# Custom_USB_N64_smaller.net
KiCad netlist of a schematic drawn in EAGLE
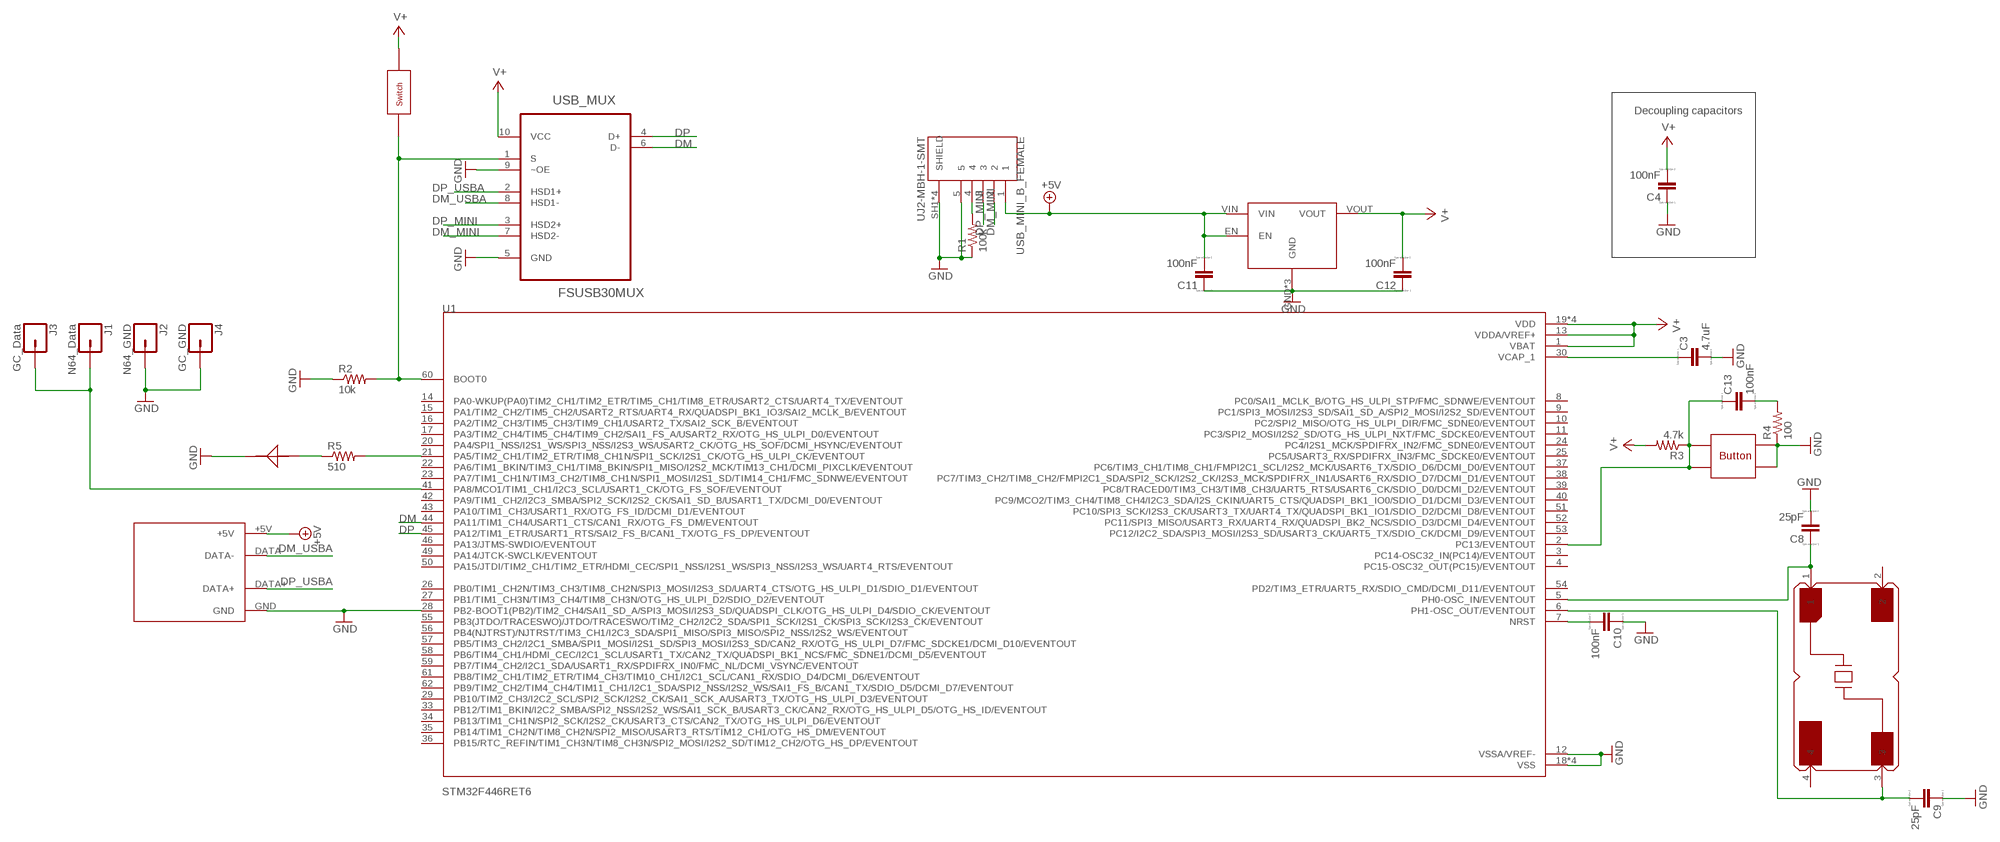
[diagram p0: schematic, sheet 1]

(export (version "E")
  (design (tool "Eeschema 10.0.6"))
  (components
    (comp (ref "C3")
      (value "4.7uF")
      (footprint "eagle-import:C0805")
      (libsource (lib "eagle-import") (part "C"))
    )
    (comp (ref "C4")
      (value "100nF")
      (footprint "eagle-import:C0805")
      (libsource (lib "eagle-import") (part "C"))
    )
    (comp (ref "C8")
      (value "25pF")
      (footprint "eagle-import:C0805")
      (libsource (lib "eagle-import") (part "C"))
    )
    (comp (ref "C9")
      (value "25pF")
      (footprint "eagle-import:C0805")
      (libsource (lib "eagle-import") (part "C"))
    )
    (comp (ref "C10")
      (value "100nF")
      (footprint "eagle-import:C0805")
      (libsource (lib "eagle-import") (part "C"))
    )
    (comp (ref "C11")
      (value "100nF")
      (footprint "eagle-import:C0805")
      (libsource (lib "eagle-import") (part "C"))
    )
    (comp (ref "C12")
      (value "100nF")
      (footprint "eagle-import:C0805")
      (libsource (lib "eagle-import") (part "C"))
    )
    (comp (ref "C13")
      (value "100nF")
      (footprint "eagle-import:C0805")
      (libsource (lib "eagle-import") (part "C"))
    )
    (comp (ref "CHANGE_CONTROLS")
      (value "PUSHBUTTON")
      (footprint "eagle-import:PUSHBUTTON")
      (libsource (lib "eagle-import") (part "PUSHBUTTON"))
    )
    (comp (ref "J1")
      (value "N64_Data")
      (footprint "eagle-import:1X01")
      (libsource (lib "eagle-import") (part "M01PTH"))
    )
    (comp (ref "J2")
      (value "N64_GND")
      (footprint "eagle-import:1X01")
      (libsource (lib "eagle-import") (part "M01PTH"))
    )
    (comp (ref "J3")
      (value "GC_Data")
      (footprint "eagle-import:1X01")
      (libsource (lib "eagle-import") (part "M01PTH"))
    )
    (comp (ref "J4")
      (value "GC_GND")
      (footprint "eagle-import:1X01")
      (libsource (lib "eagle-import") (part "M01PTH"))
    )
    (comp (ref "R1")
      (value "100k")
      (footprint "eagle-import:R0805")
      (libsource (lib "eagle-import") (part "R-US_R0805"))
    )
    (comp (ref "R2")
      (value "10k")
      (footprint "eagle-import:R0805")
      (libsource (lib "eagle-import") (part "R-US_R0805"))
    )
    (comp (ref "R3")
      (value "4.7k")
      (footprint "eagle-import:R0805")
      (libsource (lib "eagle-import") (part "R-US_R0805"))
    )
    (comp (ref "R4")
      (value "100")
      (footprint "eagle-import:R0805")
      (libsource (lib "eagle-import") (part "R-US_R0805"))
    )
    (comp (ref "R5")
      (value "510")
      (footprint "eagle-import:R0805")
      (libsource (lib "eagle-import") (part "R-US_R0805"))
    )
    (comp (ref "SWITCH")
      (value "DM01")
      (footprint "eagle-import:DM01")
      (libsource (lib "eagle-import") (part "DM01"))
    )
    (comp (ref "U$6")
      (value "17-21SYGC/S530-E2/TR8")
      (footprint "eagle-import:17-21SYGC_S530-E2_TR8")
      (libsource (lib "eagle-import") (part "17-21SYGC/S530-E2/TR8"))
    )
    (comp (ref "U1")
      (value "STM32F446RET6")
      (footprint "eagle-import:QFP50P1200X1200X160-64N")
      (fields (field (name "MF") "STMicroelectronics"))
      (libsource (lib "eagle-import") (part "STM32F446RET6"))
    )
    (comp (ref "USB_A_FEMALE")
      (value "USB_A_F")
      (footprint "eagle-import:USB_A_F")
      (libsource (lib "eagle-import") (part "USB_A_F"))
    )
    (comp (ref "USB_MINI_B_FEMALE")
      (value "UJ2-MBH-1-SMT")
      (footprint "eagle-import:CUI_UJ2-MBH-1-SMT")
      (fields (field (name "MF") "CUI") (field (name "MP") "UJ2-MBH-1-SMT-TR"))
      (libsource (lib "eagle-import") (part "UJ2-MBH-1-SMT"))
    )
    (comp (ref "USB_MUX")
      (value "FSUSB30MUX")
      (footprint "eagle-import:SOP50P490X110-10N")
      (fields (field (name "MF") "ON Semiconductor"))
      (libsource (lib "eagle-import") (part "FSUSB30MUX"))
    )
    (comp (ref "V_REG")
      (value "S-1172B33-U5T1G")
      (footprint "eagle-import:S-1172B33-U5T1G")
      (libsource (lib "eagle-import") (part "S-1172B33-U5T1G"))
    )
    (comp (ref "XTAL_HSE")
      (value "ABMM-8.000MHZ-B2-T")
      (footprint "eagle-import:DFN-4")
      (fields (field (name "MF") "Abracon"))
      (libsource (lib "eagle-import") (part "ABMM-8.000MHZ-B2-T"))
    )
  )
  (nets
    (net (code "1") (name "+5V") (class "Default")
      (node (ref "C11") (pin "2") (pinfunction "2_2") (pintype "passive"))
      (node (ref "USB_A_FEMALE") (pin "+5V") (pinfunction "+5V_+5V") (pintype "bidirectional"))
      (node (ref "USB_MINI_B_FEMALE") (pin "1") (pinfunction "1_1") (pintype "passive"))
      (node (ref "V_REG") (pin "EN") (pinfunction "EN_EN") (pintype "bidirectional"))
      (node (ref "V_REG") (pin "VIN") (pinfunction "VIN_VIN") (pintype "bidirectional"))
    )
    (net (code "2") (name "/DM") (class "Default")
      (node (ref "U1") (pin "44") (pinfunction "PA11/TIM1_CH4/USART1_CTS/CAN1_RX/OTG_FS_DM/EVENTOUT_44") (pintype "bidirectional"))
      (node (ref "USB_MUX") (pin "6") (pinfunction "D-_6") (pintype "bidirectional"))
    )
    (net (code "3") (name "/DM_MINI") (class "Default")
      (node (ref "USB_MINI_B_FEMALE") (pin "2") (pinfunction "2_2") (pintype "passive"))
      (node (ref "USB_MUX") (pin "7") (pinfunction "HSD2-_7") (pintype "bidirectional"))
    )
    (net (code "4") (name "/DM_USBA") (class "Default")
      (node (ref "USB_A_FEMALE") (pin "DATA-") (pinfunction "DATA-_DATA-") (pintype "bidirectional"))
      (node (ref "USB_MUX") (pin "8") (pinfunction "HSD1-_8") (pintype "bidirectional"))
    )
    (net (code "5") (name "/DP") (class "Default")
      (node (ref "U1") (pin "45") (pinfunction "PA12/TIM1_ETR/USART1_RTS/SAI2_FS_B/CAN1_TX/OTG_FS_DP/EVENTOUT_45") (pintype "bidirectional"))
      (node (ref "USB_MUX") (pin "4") (pinfunction "D+_4") (pintype "bidirectional"))
    )
    (net (code "6") (name "/DP_MINI") (class "Default")
      (node (ref "USB_MINI_B_FEMALE") (pin "3") (pinfunction "3_3") (pintype "passive"))
      (node (ref "USB_MUX") (pin "3") (pinfunction "HSD2+_3") (pintype "bidirectional"))
    )
    (net (code "7") (name "/DP_USBA") (class "Default")
      (node (ref "USB_A_FEMALE") (pin "DATA+") (pinfunction "DATA+_DATA+") (pintype "bidirectional"))
      (node (ref "USB_MUX") (pin "2") (pinfunction "HSD1+_2") (pintype "bidirectional"))
    )
    (net (code "8") (name "GND") (class "Default")
      (node (ref "C10") (pin "1") (pinfunction "1_1") (pintype "passive"))
      (node (ref "C11") (pin "1") (pinfunction "1_1") (pintype "passive"))
      (node (ref "C12") (pin "1") (pinfunction "1_1") (pintype "passive"))
      (node (ref "C3") (pin "2") (pinfunction "2_2") (pintype "passive"))
      (node (ref "C4") (pin "1") (pinfunction "1_1") (pintype "passive"))
      (node (ref "C8") (pin "2") (pinfunction "2_2") (pintype "passive"))
      (node (ref "C9") (pin "1") (pinfunction "1_1") (pintype "passive"))
      (node (ref "CHANGE_CONTROLS") (pin "P$3") (pinfunction "P$3_P$3") (pintype "bidirectional"))
      (node (ref "CHANGE_CONTROLS") (pin "P$4") (pinfunction "P$4_P$4") (pintype "bidirectional"))
      (node (ref "J2") (pin "1") (pinfunction "1_1") (pintype "passive"))
      (node (ref "J4") (pin "1") (pinfunction "1_1") (pintype "passive"))
      (node (ref "R1") (pin "1") (pinfunction "1_1") (pintype "passive"))
      (node (ref "R2") (pin "1") (pinfunction "1_1") (pintype "passive"))
      (node (ref "R4") (pin "1") (pinfunction "1_1") (pintype "passive"))
      (node (ref "U$6") (pin "NEG") (pinfunction "NEG_NEG") (pintype "bidirectional"))
      (node (ref "U1") (pin "12") (pinfunction "VSSA/VREF-_12") (pintype "power_in"))
      (node (ref "U1") (pin "18") (pinfunction "VSS_18") (pintype "power_in"))
      (node (ref "U1") (pin "28") (pinfunction "PB2-BOOT1(PB2)/TIM2_CH4/SAI1_SD_A/SPI3_MOSI/I2S3_SD/QUADSPI_CLK/OTG_HS_ULPI_D4/SDIO_CK/EVENTOUT_28") (pintype "bidirectional"))
      (node (ref "U1") (pin "31") (pinfunction "VSS_31") (pintype "power_in"))
      (node (ref "U1") (pin "47") (pinfunction "VSS_47") (pintype "power_in"))
      (node (ref "U1") (pin "63") (pinfunction "VSS_63") (pintype "power_in"))
      (node (ref "USB_A_FEMALE") (pin "GND") (pinfunction "GND_GND") (pintype "bidirectional"))
      (node (ref "USB_MINI_B_FEMALE") (pin "5") (pinfunction "5_5") (pintype "passive"))
      (node (ref "USB_MINI_B_FEMALE") (pin "SH1") (pinfunction "SHIELD_SH1") (pintype "passive"))
      (node (ref "USB_MINI_B_FEMALE") (pin "SH2") (pinfunction "SHIELD_SH2") (pintype "passive"))
      (node (ref "USB_MINI_B_FEMALE") (pin "SH3") (pinfunction "SHIELD_SH3") (pintype "passive"))
      (node (ref "USB_MINI_B_FEMALE") (pin "SH4") (pinfunction "SHIELD_SH4") (pintype "passive"))
      (node (ref "USB_MUX") (pin "5") (pinfunction "GND_5") (pintype "passive"))
      (node (ref "USB_MUX") (pin "9") (pinfunction "~{OE}_9") (pintype "input"))
      (node (ref "V_REG") (pin "GND") (pinfunction "GND_GND") (pintype "bidirectional"))
      (node (ref "V_REG") (pin "GND2") (pinfunction "GND_GND2") (pintype "bidirectional"))
      (node (ref "V_REG") (pin "GND3") (pinfunction "GND_GND3") (pintype "bidirectional"))
    )
    (net (code "9") (name "Net-(C13-Pad2)") (class "Default")
      (node (ref "C13") (pin "2") (pinfunction "2_2") (pintype "passive"))
      (node (ref "R4") (pin "2") (pinfunction "2_2") (pintype "passive"))
    )
    (net (code "10") (name "Net-(R1-Pad2)") (class "Default")
      (node (ref "R1") (pin "2") (pinfunction "2_2") (pintype "passive"))
      (node (ref "USB_MINI_B_FEMALE") (pin "4") (pinfunction "4_4") (pintype "passive"))
    )
    (net (code "11") (name "Net-(R5-Pad1)") (class "Default")
      (node (ref "R5") (pin "1") (pinfunction "1_1") (pintype "passive"))
      (node (ref "U$6") (pin "POS") (pinfunction "POS_POS") (pintype "bidirectional"))
    )
    (net (code "12") (name "Net-(U1-BOOT0)") (class "Default")
      (node (ref "R2") (pin "2") (pinfunction "2_2") (pintype "passive"))
      (node (ref "SWITCH") (pin "P$2") (pinfunction "P$2_P$2") (pintype "bidirectional"))
      (node (ref "U1") (pin "60") (pinfunction "BOOT0_60") (pintype "input"))
      (node (ref "USB_MUX") (pin "1") (pinfunction "S_1") (pintype "input"))
    )
    (net (code "13") (name "Net-(U1-NRST)") (class "Default")
      (node (ref "C10") (pin "2") (pinfunction "2_2") (pintype "passive"))
      (node (ref "U1") (pin "7") (pinfunction "NRST_7") (pintype "bidirectional"))
    )
    (net (code "14") (name "Net-(U1-PA5{slash}TIM2_CH1{slash}TIM2_ETR{slash}TIM8_CH1N{slash}SPI1_SCK{slash}I2S1_CK{slash}OTG_HS_ULPI_CK{slash}EVENTOUT)") (class "Default")
      (node (ref "R5") (pin "2") (pinfunction "2_2") (pintype "passive"))
      (node (ref "U1") (pin "21") (pinfunction "PA5/TIM2_CH1/TIM2_ETR/TIM8_CH1N/SPI1_SCK/I2S1_CK/OTG_HS_ULPI_CK/EVENTOUT_21") (pintype "bidirectional"))
    )
    (net (code "15") (name "Net-(U1-PA8{slash}MCO1{slash}TIM1_CH1{slash}I2C3_SCL{slash}USART1_CK{slash}OTG_FS_SOF{slash}EVENTOUT)") (class "Default")
      (node (ref "J1") (pin "1") (pinfunction "1_1") (pintype "passive"))
      (node (ref "J3") (pin "1") (pinfunction "1_1") (pintype "passive"))
      (node (ref "U1") (pin "41") (pinfunction "PA8/MCO1/TIM1_CH1/I2C3_SCL/USART1_CK/OTG_FS_SOF/EVENTOUT_41") (pintype "bidirectional"))
    )
    (net (code "16") (name "Net-(U1-PC13{slash}EVENTOUT)") (class "Default")
      (node (ref "C13") (pin "1") (pinfunction "1_1") (pintype "passive"))
      (node (ref "CHANGE_CONTROLS") (pin "P$1") (pinfunction "P$1_P$1") (pintype "bidirectional"))
      (node (ref "CHANGE_CONTROLS") (pin "P$2") (pinfunction "P$2_P$2") (pintype "bidirectional"))
      (node (ref "R3") (pin "1") (pinfunction "1_1") (pintype "passive"))
      (node (ref "U1") (pin "2") (pinfunction "PC13/EVENTOUT_2") (pintype "bidirectional"))
    )
    (net (code "17") (name "Net-(U1-PH0-OSC_IN{slash}EVENTOUT)") (class "Default")
      (node (ref "C8") (pin "1") (pinfunction "1_1") (pintype "passive"))
      (node (ref "U1") (pin "5") (pinfunction "PH0-OSC_IN/EVENTOUT_5") (pintype "bidirectional"))
      (node (ref "XTAL_HSE") (pin "1") (pinfunction "1_1") (pintype "bidirectional"))
    )
    (net (code "18") (name "Net-(U1-PH1-OSC_OUT{slash}EVENTOUT)") (class "Default")
      (node (ref "C9") (pin "2") (pinfunction "2_2") (pintype "passive"))
      (node (ref "U1") (pin "6") (pinfunction "PH1-OSC_OUT/EVENTOUT_6") (pintype "bidirectional"))
      (node (ref "XTAL_HSE") (pin "3") (pinfunction "3_3") (pintype "bidirectional"))
    )
    (net (code "19") (name "Net-(U1-VCAP_1)") (class "Default")
      (node (ref "C3") (pin "1") (pinfunction "1_1") (pintype "passive"))
      (node (ref "U1") (pin "30") (pinfunction "VCAP_1_30") (pintype "power_in"))
    )
    (net (code "20") (name "V+") (class "Default")
      (node (ref "C12") (pin "2") (pinfunction "2_2") (pintype "passive"))
      (node (ref "C4") (pin "2") (pinfunction "2_2") (pintype "passive"))
      (node (ref "R3") (pin "2") (pinfunction "2_2") (pintype "passive"))
      (node (ref "SWITCH") (pin "P$1") (pinfunction "P$1_P$1") (pintype "bidirectional"))
      (node (ref "U1") (pin "1") (pinfunction "VBAT_1") (pintype "power_in"))
      (node (ref "U1") (pin "13") (pinfunction "VDDA/VREF+_13") (pintype "power_in"))
      (node (ref "U1") (pin "19") (pinfunction "VDD_19") (pintype "power_in"))
      (node (ref "U1") (pin "32") (pinfunction "VDD_32") (pintype "power_in"))
      (node (ref "U1") (pin "48") (pinfunction "VDD_48") (pintype "power_in"))
      (node (ref "U1") (pin "64") (pinfunction "VDD_64") (pintype "power_in"))
      (node (ref "USB_MUX") (pin "10") (pinfunction "VCC_10") (pintype "power_in"))
      (node (ref "V_REG") (pin "VOUT") (pinfunction "VOUT_VOUT") (pintype "bidirectional"))
    )
    (net (code "21") (name "unconnected-(U1-PA0-WKUP(PA0)TIM2_CH1{slash}TIM2_ETR{slash}TIM5_CH1{slash}TIM8_ETR{slash}USART2_CTS{slash}UART4_TX{slash}EVENTOUT-Pad14)") (class "Default")
      (node (ref "U1") (pin "14") (pinfunction "PA0-WKUP(PA0)TIM2_CH1/TIM2_ETR/TIM5_CH1/TIM8_ETR/USART2_CTS/UART4_TX/EVENTOUT_14") (pintype "bidirectional"))
    )
    (net (code "22") (name "unconnected-(U1-PA1{slash}TIM2_CH2{slash}TIM5_CH2{slash}USART2_RTS{slash}UART4_RX{slash}QUADSPI_BK1_IO3{slash}SAI2_MCLK_B{slash}EVENTOUT-Pad15)") (class "Default")
      (node (ref "U1") (pin "15") (pinfunction "PA1/TIM2_CH2/TIM5_CH2/USART2_RTS/UART4_RX/QUADSPI_BK1_IO3/SAI2_MCLK_B/EVENTOUT_15") (pintype "bidirectional"))
    )
    (net (code "23") (name "unconnected-(U1-PA2{slash}TIM2_CH3{slash}TIM5_CH3{slash}TIM9_CH1{slash}USART2_TX{slash}SAI2_SCK_B{slash}EVENTOUT-Pad16)") (class "Default")
      (node (ref "U1") (pin "16") (pinfunction "PA2/TIM2_CH3/TIM5_CH3/TIM9_CH1/USART2_TX/SAI2_SCK_B/EVENTOUT_16") (pintype "bidirectional"))
    )
    (net (code "24") (name "unconnected-(U1-PA3{slash}TIM2_CH4{slash}TIM5_CH4{slash}TIM9_CH2{slash}SAI1_FS_A{slash}USART2_RX{slash}OTG_HS_ULPI_D0{slash}EVENTOUT-Pad17)") (class "Default")
      (node (ref "U1") (pin "17") (pinfunction "PA3/TIM2_CH4/TIM5_CH4/TIM9_CH2/SAI1_FS_A/USART2_RX/OTG_HS_ULPI_D0/EVENTOUT_17") (pintype "bidirectional"))
    )
    (net (code "25") (name "unconnected-(U1-PA4{slash}SPI1_NSS{slash}I2S1_WS{slash}SPI3_NSS{slash}I2S3_WS{slash}USART2_CK{slash}OTG_HS_SOF{slash}DCMI_HSYNC{slash}EVENTOUT-Pad20)") (class "Default")
      (node (ref "U1") (pin "20") (pinfunction "PA4/SPI1_NSS/I2S1_WS/SPI3_NSS/I2S3_WS/USART2_CK/OTG_HS_SOF/DCMI_HSYNC/EVENTOUT_20") (pintype "bidirectional"))
    )
    (net (code "26") (name "unconnected-(U1-PA6{slash}TIM1_BKIN{slash}TIM3_CH1{slash}TIM8_BKIN{slash}SPI1_MISO{slash}I2S2_MCK{slash}TIM13_CH1{slash}DCMI_PIXCLK{slash}EVENTOUT-Pad22)") (class "Default")
      (node (ref "U1") (pin "22") (pinfunction "PA6/TIM1_BKIN/TIM3_CH1/TIM8_BKIN/SPI1_MISO/I2S2_MCK/TIM13_CH1/DCMI_PIXCLK/EVENTOUT_22") (pintype "bidirectional"))
    )
    (net (code "27") (name "unconnected-(U1-PA7{slash}TIM1_CH1N{slash}TIM3_CH2{slash}TIM8_CH1N{slash}SPI1_MOSI{slash}I2S1_SD{slash}TIM14_CH1{slash}FMC_SDNWE{slash}EVENTOUT-Pad23)") (class "Default")
      (node (ref "U1") (pin "23") (pinfunction "PA7/TIM1_CH1N/TIM3_CH2/TIM8_CH1N/SPI1_MOSI/I2S1_SD/TIM14_CH1/FMC_SDNWE/EVENTOUT_23") (pintype "bidirectional"))
    )
    (net (code "28") (name "unconnected-(U1-PA9{slash}TIM1_CH2{slash}I2C3_SMBA{slash}SPI2_SCK{slash}I2S2_CK{slash}SAI1_SD_B{slash}USART1_TX{slash}DCMI_D0{slash}EVENTOUT-Pad42)") (class "Default")
      (node (ref "U1") (pin "42") (pinfunction "PA9/TIM1_CH2/I2C3_SMBA/SPI2_SCK/I2S2_CK/SAI1_SD_B/USART1_TX/DCMI_D0/EVENTOUT_42") (pintype "bidirectional"))
    )
    (net (code "29") (name "unconnected-(U1-PA10{slash}TIM1_CH3{slash}USART1_RX{slash}OTG_FS_ID{slash}DCMI_D1{slash}EVENTOUT-Pad43)") (class "Default")
      (node (ref "U1") (pin "43") (pinfunction "PA10/TIM1_CH3/USART1_RX/OTG_FS_ID/DCMI_D1/EVENTOUT_43") (pintype "bidirectional"))
    )
    (net (code "30") (name "unconnected-(U1-PA13{slash}JTMS-SWDIO{slash}EVENTOUT-Pad46)") (class "Default")
      (node (ref "U1") (pin "46") (pinfunction "PA13/JTMS-SWDIO/EVENTOUT_46") (pintype "bidirectional"))
    )
    (net (code "31") (name "unconnected-(U1-PA14{slash}JTCK-SWCLK{slash}EVENTOUT-Pad49)") (class "Default")
      (node (ref "U1") (pin "49") (pinfunction "PA14/JTCK-SWCLK/EVENTOUT_49") (pintype "bidirectional"))
    )
    (net (code "32") (name "unconnected-(U1-PA15{slash}JTDI{slash}TIM2_CH1{slash}TIM2_ETR{slash}HDMI_CEC{slash}SPI1_NSS{slash}I2S1_WS{slash}SPI3_NSS{slash}I2S3_WS{slash}UART4_RTS{slash}EVENTOUT-Pad50)") (class "Default")
      (node (ref "U1") (pin "50") (pinfunction "PA15/JTDI/TIM2_CH1/TIM2_ETR/HDMI_CEC/SPI1_NSS/I2S1_WS/SPI3_NSS/I2S3_WS/UART4_RTS/EVENTOUT_50") (pintype "bidirectional"))
    )
    (net (code "33") (name "unconnected-(U1-PB0{slash}TIM1_CH2N{slash}TIM3_CH3{slash}TIM8_CH2N{slash}SPI3_MOSI{slash}I2S3_SD{slash}UART4_CTS{slash}OTG_HS_ULPI_D1{slash}SDIO_D1{slash}EVENTOUT-Pad26)") (class "Default")
      (node (ref "U1") (pin "26") (pinfunction "PB0/TIM1_CH2N/TIM3_CH3/TIM8_CH2N/SPI3_MOSI/I2S3_SD/UART4_CTS/OTG_HS_ULPI_D1/SDIO_D1/EVENTOUT_26") (pintype "bidirectional"))
    )
    (net (code "34") (name "unconnected-(U1-PB1{slash}TIM1_CH3N{slash}TIM3_CH4{slash}TIM8_CH3N{slash}OTG_HS_ULPI_D2{slash}SDIO_D2{slash}EVENTOUT-Pad27)") (class "Default")
      (node (ref "U1") (pin "27") (pinfunction "PB1/TIM1_CH3N/TIM3_CH4/TIM8_CH3N/OTG_HS_ULPI_D2/SDIO_D2/EVENTOUT_27") (pintype "bidirectional"))
    )
    (net (code "35") (name "unconnected-(U1-PB3(JTDO{slash}TRACESWO){slash}JTDO{slash}TRACESWO{slash}TIM2_CH2{slash}I2C2_SDA{slash}SPI1_SCK{slash}I2S1_CK{slash}SPI3_SCK{slash}I2S3_CK{slash}EVENTOUT-Pad55)") (class "Default")
      (node (ref "U1") (pin "55") (pinfunction "PB3(JTDO/TRACESWO)/JTDO/TRACESWO/TIM2_CH2/I2C2_SDA/SPI1_SCK/I2S1_CK/SPI3_SCK/I2S3_CK/EVENTOUT_55") (pintype "bidirectional"))
    )
    (net (code "36") (name "unconnected-(U1-PB4(NJTRST){slash}NJTRST{slash}TIM3_CH1{slash}I2C3_SDA{slash}SPI1_MISO{slash}SPI3_MISO{slash}SPI2_NSS{slash}I2S2_WS{slash}EVENTOUT-Pad56)") (class "Default")
      (node (ref "U1") (pin "56") (pinfunction "PB4(NJTRST)/NJTRST/TIM3_CH1/I2C3_SDA/SPI1_MISO/SPI3_MISO/SPI2_NSS/I2S2_WS/EVENTOUT_56") (pintype "bidirectional"))
    )
    (net (code "37") (name "unconnected-(U1-PB5{slash}TIM3_CH2{slash}I2C1_SMBA{slash}SPI1_MOSI{slash}I2S1_SD{slash}SPI3_MOSI{slash}I2S3_SD{slash}CAN2_RX{slash}OTG_HS_ULPI_D7{slash}FMC_SDCKE1{slash}DCMI_D10{slash}EVENTOUT-Pad57)") (class "Default")
      (node (ref "U1") (pin "57") (pinfunction "PB5/TIM3_CH2/I2C1_SMBA/SPI1_MOSI/I2S1_SD/SPI3_MOSI/I2S3_SD/CAN2_RX/OTG_HS_ULPI_D7/FMC_SDCKE1/DCMI_D10/EVENTOUT_57") (pintype "bidirectional"))
    )
    (net (code "38") (name "unconnected-(U1-PB6{slash}TIM4_CH1{slash}HDMI_CEC{slash}I2C1_SCL{slash}USART1_TX{slash}CAN2_TX{slash}QUADSPI_BK1_NCS{slash}FMC_SDNE1{slash}DCMI_D5{slash}EVENTOUT-Pad58)") (class "Default")
      (node (ref "U1") (pin "58") (pinfunction "PB6/TIM4_CH1/HDMI_CEC/I2C1_SCL/USART1_TX/CAN2_TX/QUADSPI_BK1_NCS/FMC_SDNE1/DCMI_D5/EVENTOUT_58") (pintype "bidirectional"))
    )
    (net (code "39") (name "unconnected-(U1-PB7{slash}TIM4_CH2{slash}I2C1_SDA{slash}USART1_RX{slash}SPDIFRX_IN0{slash}FMC_NL{slash}DCMI_VSYNC{slash}EVENTOUT-Pad59)") (class "Default")
      (node (ref "U1") (pin "59") (pinfunction "PB7/TIM4_CH2/I2C1_SDA/USART1_RX/SPDIFRX_IN0/FMC_NL/DCMI_VSYNC/EVENTOUT_59") (pintype "bidirectional"))
    )
    (net (code "40") (name "unconnected-(U1-PB8{slash}TIM2_CH1{slash}TIM2_ETR{slash}TIM4_CH3{slash}TIM10_CH1{slash}I2C1_SCL{slash}CAN1_RX{slash}SDIO_D4{slash}DCMI_D6{slash}EVENTOUT-Pad61)") (class "Default")
      (node (ref "U1") (pin "61") (pinfunction "PB8/TIM2_CH1/TIM2_ETR/TIM4_CH3/TIM10_CH1/I2C1_SCL/CAN1_RX/SDIO_D4/DCMI_D6/EVENTOUT_61") (pintype "bidirectional"))
    )
    (net (code "41") (name "unconnected-(U1-PB9{slash}TIM2_CH2{slash}TIM4_CH4{slash}TIM11_CH1{slash}I2C1_SDA{slash}SPI2_NSS{slash}I2S2_WS{slash}SAI1_FS_B{slash}CAN1_TX{slash}SDIO_D5{slash}DCMI_D7{slash}EVENTOUT-Pad62)") (class "Default")
      (node (ref "U1") (pin "62") (pinfunction "PB9/TIM2_CH2/TIM4_CH4/TIM11_CH1/I2C1_SDA/SPI2_NSS/I2S2_WS/SAI1_FS_B/CAN1_TX/SDIO_D5/DCMI_D7/EVENTOUT_62") (pintype "bidirectional"))
    )
    (net (code "42") (name "unconnected-(U1-PB10{slash}TIM2_CH3{slash}I2C2_SCL{slash}SPI2_SCK{slash}I2S2_CK{slash}SAI1_SCK_A{slash}USART3_TX{slash}OTG_HS_ULPI_D3{slash}EVENTOUT-Pad29)") (class "Default")
      (node (ref "U1") (pin "29") (pinfunction "PB10/TIM2_CH3/I2C2_SCL/SPI2_SCK/I2S2_CK/SAI1_SCK_A/USART3_TX/OTG_HS_ULPI_D3/EVENTOUT_29") (pintype "bidirectional"))
    )
    (net (code "43") (name "unconnected-(U1-PB12{slash}TIM1_BKIN{slash}I2C2_SMBA{slash}SPI2_NSS{slash}I2S2_WS{slash}SAI1_SCK_B{slash}USART3_CK{slash}CAN2_RX{slash}OTG_HS_ULPI_D5{slash}OTG_HS_ID{slash}EVENTOUT-Pad33)") (class "Default")
      (node (ref "U1") (pin "33") (pinfunction "PB12/TIM1_BKIN/I2C2_SMBA/SPI2_NSS/I2S2_WS/SAI1_SCK_B/USART3_CK/CAN2_RX/OTG_HS_ULPI_D5/OTG_HS_ID/EVENTOUT_33") (pintype "bidirectional"))
    )
    (net (code "44") (name "unconnected-(U1-PB13{slash}TIM1_CH1N{slash}SPI2_SCK{slash}I2S2_CK{slash}USART3_CTS{slash}CAN2_TX{slash}OTG_HS_ULPI_D6{slash}EVENTOUT-Pad34)") (class "Default")
      (node (ref "U1") (pin "34") (pinfunction "PB13/TIM1_CH1N/SPI2_SCK/I2S2_CK/USART3_CTS/CAN2_TX/OTG_HS_ULPI_D6/EVENTOUT_34") (pintype "bidirectional"))
    )
    (net (code "45") (name "unconnected-(U1-PB14{slash}TIM1_CH2N{slash}TIM8_CH2N{slash}SPI2_MISO{slash}USART3_RTS{slash}TIM12_CH1{slash}OTG_HS_DM{slash}EVENTOUT-Pad35)") (class "Default")
      (node (ref "U1") (pin "35") (pinfunction "PB14/TIM1_CH2N/TIM8_CH2N/SPI2_MISO/USART3_RTS/TIM12_CH1/OTG_HS_DM/EVENTOUT_35") (pintype "bidirectional"))
    )
    (net (code "46") (name "unconnected-(U1-PB15{slash}RTC_REFIN{slash}TIM1_CH3N{slash}TIM8_CH3N{slash}SPI2_MOSI{slash}I2S2_SD{slash}TIM12_CH2{slash}OTG_HS_DP{slash}EVENTOUT-Pad36)") (class "Default")
      (node (ref "U1") (pin "36") (pinfunction "PB15/RTC_REFIN/TIM1_CH3N/TIM8_CH3N/SPI2_MOSI/I2S2_SD/TIM12_CH2/OTG_HS_DP/EVENTOUT_36") (pintype "bidirectional"))
    )
    (net (code "47") (name "unconnected-(U1-PC0{slash}SAI1_MCLK_B{slash}OTG_HS_ULPI_STP{slash}FMC_SDNWE{slash}EVENTOUT-Pad8)") (class "Default")
      (node (ref "U1") (pin "8") (pinfunction "PC0/SAI1_MCLK_B/OTG_HS_ULPI_STP/FMC_SDNWE/EVENTOUT_8") (pintype "bidirectional"))
    )
    (net (code "48") (name "unconnected-(U1-PC1{slash}SPI3_MOSI{slash}I2S3_SD{slash}SAI1_SD_A{slash}SPI2_MOSI{slash}I2S2_SD{slash}EVENTOUT-Pad9)") (class "Default")
      (node (ref "U1") (pin "9") (pinfunction "PC1/SPI3_MOSI/I2S3_SD/SAI1_SD_A/SPI2_MOSI/I2S2_SD/EVENTOUT_9") (pintype "bidirectional"))
    )
    (net (code "49") (name "unconnected-(U1-PC2{slash}SPI2_MISO{slash}OTG_HS_ULPI_DIR{slash}FMC_SDNE0{slash}EVENTOUT-Pad10)") (class "Default")
      (node (ref "U1") (pin "10") (pinfunction "PC2/SPI2_MISO/OTG_HS_ULPI_DIR/FMC_SDNE0/EVENTOUT_10") (pintype "bidirectional"))
    )
    (net (code "50") (name "unconnected-(U1-PC3{slash}SPI2_MOSI{slash}I2S2_SD{slash}OTG_HS_ULPI_NXT{slash}FMC_SDCKE0{slash}EVENTOUT-Pad11)") (class "Default")
      (node (ref "U1") (pin "11") (pinfunction "PC3/SPI2_MOSI/I2S2_SD/OTG_HS_ULPI_NXT/FMC_SDCKE0/EVENTOUT_11") (pintype "bidirectional"))
    )
    (net (code "51") (name "unconnected-(U1-PC4{slash}I2S1_MCK{slash}SPDIFRX_IN2{slash}FMC_SDNE0{slash}EVENTOUT-Pad24)") (class "Default")
      (node (ref "U1") (pin "24") (pinfunction "PC4/I2S1_MCK/SPDIFRX_IN2/FMC_SDNE0/EVENTOUT_24") (pintype "bidirectional"))
    )
    (net (code "52") (name "unconnected-(U1-PC5{slash}USART3_RX{slash}SPDIFRX_IN3{slash}FMC_SDCKE0{slash}EVENTOUT-Pad25)") (class "Default")
      (node (ref "U1") (pin "25") (pinfunction "PC5/USART3_RX/SPDIFRX_IN3/FMC_SDCKE0/EVENTOUT_25") (pintype "bidirectional"))
    )
    (net (code "53") (name "unconnected-(U1-PC6{slash}TIM3_CH1{slash}TIM8_CH1{slash}FMPI2C1_SCL{slash}I2S2_MCK{slash}USART6_TX{slash}SDIO_D6{slash}DCMI_D0{slash}EVENTOUT-Pad37)") (class "Default")
      (node (ref "U1") (pin "37") (pinfunction "PC6/TIM3_CH1/TIM8_CH1/FMPI2C1_SCL/I2S2_MCK/USART6_TX/SDIO_D6/DCMI_D0/EVENTOUT_37") (pintype "bidirectional"))
    )
    (net (code "54") (name "unconnected-(U1-PC7{slash}TIM3_CH2{slash}TIM8_CH2{slash}FMPI2C1_SDA{slash}SPI2_SCK{slash}I2S2_CK{slash}I2S3_MCK{slash}SPDIFRX_IN1{slash}USART6_RX{slash}SDIO_D7{slash}DCMI_D1{slash}EVENTOUT-Pad38)") (class "Default")
      (node (ref "U1") (pin "38") (pinfunction "PC7/TIM3_CH2/TIM8_CH2/FMPI2C1_SDA/SPI2_SCK/I2S2_CK/I2S3_MCK/SPDIFRX_IN1/USART6_RX/SDIO_D7/DCMI_D1/EVENTOUT_38") (pintype "bidirectional"))
    )
    (net (code "55") (name "unconnected-(U1-PC8{slash}TRACED0{slash}TIM3_CH3{slash}TIM8_CH3{slash}UART5_RTS{slash}USART6_CK{slash}SDIO_D0{slash}DCMI_D2{slash}EVENTOUT-Pad39)") (class "Default")
      (node (ref "U1") (pin "39") (pinfunction "PC8/TRACED0/TIM3_CH3/TIM8_CH3/UART5_RTS/USART6_CK/SDIO_D0/DCMI_D2/EVENTOUT_39") (pintype "bidirectional"))
    )
    (net (code "56") (name "unconnected-(U1-PC9{slash}MCO2{slash}TIM3_CH4{slash}TIM8_CH4{slash}I2C3_SDA{slash}I2S_CKIN{slash}UART5_CTS{slash}QUADSPI_BK1_IO0{slash}SDIO_D1{slash}DCMI_D3{slash}EVENTOUT-Pad40)") (class "Default")
      (node (ref "U1") (pin "40") (pinfunction "PC9/MCO2/TIM3_CH4/TIM8_CH4/I2C3_SDA/I2S_CKIN/UART5_CTS/QUADSPI_BK1_IO0/SDIO_D1/DCMI_D3/EVENTOUT_40") (pintype "bidirectional"))
    )
    (net (code "57") (name "unconnected-(U1-PC10{slash}SPI3_SCK{slash}I2S3_CK{slash}USART3_TX{slash}UART4_TX{slash}QUADSPI_BK1_IO1{slash}SDIO_D2{slash}DCMI_D8{slash}EVENTOUT-Pad51)") (class "Default")
      (node (ref "U1") (pin "51") (pinfunction "PC10/SPI3_SCK/I2S3_CK/USART3_TX/UART4_TX/QUADSPI_BK1_IO1/SDIO_D2/DCMI_D8/EVENTOUT_51") (pintype "bidirectional"))
    )
    (net (code "58") (name "unconnected-(U1-PC11{slash}SPI3_MISO{slash}USART3_RX{slash}UART4_RX{slash}QUADSPI_BK2_NCS{slash}SDIO_D3{slash}DCMI_D4{slash}EVENTOUT-Pad52)") (class "Default")
      (node (ref "U1") (pin "52") (pinfunction "PC11/SPI3_MISO/USART3_RX/UART4_RX/QUADSPI_BK2_NCS/SDIO_D3/DCMI_D4/EVENTOUT_52") (pintype "bidirectional"))
    )
    (net (code "59") (name "unconnected-(U1-PC12{slash}I2C2_SDA{slash}SPI3_MOSI{slash}I2S3_SD{slash}USART3_CK{slash}UART5_TX{slash}SDIO_CK{slash}DCMI_D9{slash}EVENTOUT-Pad53)") (class "Default")
      (node (ref "U1") (pin "53") (pinfunction "PC12/I2C2_SDA/SPI3_MOSI/I2S3_SD/USART3_CK/UART5_TX/SDIO_CK/DCMI_D9/EVENTOUT_53") (pintype "bidirectional"))
    )
    (net (code "60") (name "unconnected-(U1-PC14-OSC32_IN(PC14){slash}EVENTOUT-Pad3)") (class "Default")
      (node (ref "U1") (pin "3") (pinfunction "PC14-OSC32_IN(PC14)/EVENTOUT_3") (pintype "bidirectional"))
    )
    (net (code "61") (name "unconnected-(U1-PC15-OSC32_OUT(PC15){slash}EVENTOUT-Pad4)") (class "Default")
      (node (ref "U1") (pin "4") (pinfunction "PC15-OSC32_OUT(PC15)/EVENTOUT_4") (pintype "bidirectional"))
    )
    (net (code "62") (name "unconnected-(U1-PD2{slash}TIM3_ETR{slash}UART5_RX{slash}SDIO_CMD{slash}DCMI_D11{slash}EVENTOUT-Pad54)") (class "Default")
      (node (ref "U1") (pin "54") (pinfunction "PD2/TIM3_ETR/UART5_RX/SDIO_CMD/DCMI_D11/EVENTOUT_54") (pintype "bidirectional"))
    )
    (net (code "63") (name "unconnected-(XTAL_HSE-Pad2)") (class "Default")
      (node (ref "XTAL_HSE") (pin "2") (pinfunction "2_2") (pintype "bidirectional"))
    )
    (net (code "64") (name "unconnected-(XTAL_HSE-Pad4)") (class "Default")
      (node (ref "XTAL_HSE") (pin "4") (pinfunction "4_4") (pintype "bidirectional"))
    )
  )
)
